# LaunchpadRJ11Baseboard_Mk2.net
KiCad netlist of a schematic drawn in EAGLE
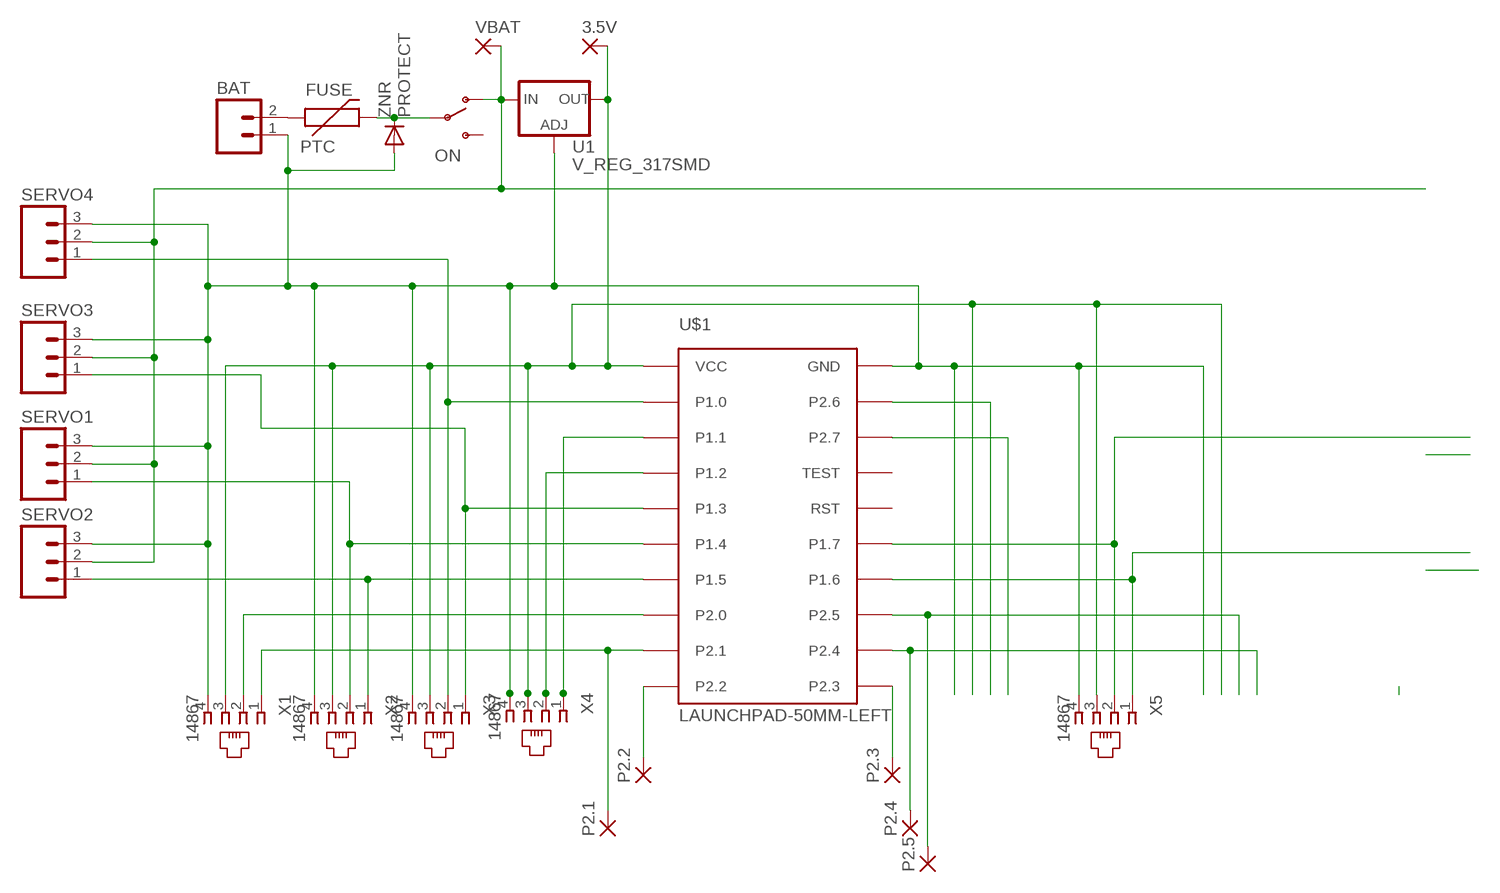
[diagram p0: schematic, sheet 1]

(export (version "E")
  (design (tool "Eeschema 10.0.6"))
  (components
    (comp (ref "3.5V")
      (value "2,15/1,0")
      (footprint "eagle-import:2,15_1,0")
      (libsource (lib "eagle-import") (part "2,15/1,0"))
    )
    (comp (ref "BAT")
      (value "M02PTH")
      (footprint "eagle-import:1X02")
      (libsource (lib "eagle-import") (part "M02PTH"))
    )
    (comp (ref "FUSE")
      (value "PTC")
      (footprint "eagle-import:PTC")
      (libsource (lib "eagle-import") (part "PTCPTH"))
    )
    (comp (ref "ON")
      (value "SWITCH-SPSTPTH")
      (footprint "eagle-import:SWITCH-SPDT")
      (libsource (lib "eagle-import") (part "SWITCH-SPSTPTH"))
    )
    (comp (ref "P2.1")
      (value "2,15/1,0")
      (footprint "eagle-import:2,15_1,0")
      (libsource (lib "eagle-import") (part "2,15/1,0"))
    )
    (comp (ref "P2.2")
      (value "2,15/1,0")
      (footprint "eagle-import:2,15_1,0")
      (libsource (lib "eagle-import") (part "2,15/1,0"))
    )
    (comp (ref "P2.3")
      (value "2,15/1,0")
      (footprint "eagle-import:2,15_1,0")
      (libsource (lib "eagle-import") (part "2,15/1,0"))
    )
    (comp (ref "P2.4")
      (value "2,15/1,0")
      (footprint "eagle-import:2,15_1,0")
      (libsource (lib "eagle-import") (part "2,15/1,0"))
    )
    (comp (ref "P2.5")
      (value "2,15/1,0")
      (footprint "eagle-import:2,15_1,0")
      (libsource (lib "eagle-import") (part "2,15/1,0"))
    )
    (comp (ref "SERVO1")
      (value "M03PTH")
      (footprint "eagle-import:1X03")
      (libsource (lib "eagle-import") (part "M03PTH"))
    )
    (comp (ref "SERVO2")
      (value "M03PTH")
      (footprint "eagle-import:1X03")
      (libsource (lib "eagle-import") (part "M03PTH"))
    )
    (comp (ref "SERVO3")
      (value "M03PTH")
      (footprint "eagle-import:1X03")
      (libsource (lib "eagle-import") (part "M03PTH"))
    )
    (comp (ref "SERVO4")
      (value "M03PTH")
      (footprint "eagle-import:1X03")
      (libsource (lib "eagle-import") (part "M03PTH"))
    )
    (comp (ref "U$1")
      (value "LAUNCHPAD-50MM-LEFT")
      (footprint "eagle-import:LAUNCHPAD-50MM-LEFT")
      (libsource (lib "eagle-import") (part "LAUNCHPAD-50MM-LEFT"))
    )
    (comp (ref "U1")
      (value "V_REG_317SMD")
      (footprint "eagle-import:SOT223")
      (libsource (lib "eagle-import") (part "V_REG_317SMD"))
    )
    (comp (ref "VBAT")
      (value "2,15/1,0")
      (footprint "eagle-import:2,15_1,0")
      (libsource (lib "eagle-import") (part "2,15/1,0"))
    )
    (comp (ref "X1")
      (value "14867")
      (footprint "eagle-import:14867")
      (libsource (lib "eagle-import") (part "14867"))
    )
    (comp (ref "X2")
      (value "14867")
      (footprint "eagle-import:14867")
      (fields (field (name "OC_FARNELL") "unknown") (field (name "OC_NEWARK") "unknown"))
      (libsource (lib "eagle-import") (part "14867"))
    )
    (comp (ref "X3")
      (value "14867")
      (footprint "eagle-import:14867")
      (fields (field (name "OC_FARNELL") "unknown") (field (name "OC_NEWARK") "unknown"))
      (libsource (lib "eagle-import") (part "14867"))
    )
    (comp (ref "X4")
      (value "14867")
      (footprint "eagle-import:14867")
      (fields (field (name "OC_FARNELL") "unknown") (field (name "OC_NEWARK") "unknown"))
      (libsource (lib "eagle-import") (part "14867"))
    )
    (comp (ref "X5")
      (value "14867")
      (footprint "eagle-import:14867")
      (fields (field (name "OC_FARNELL") "unknown") (field (name "OC_NEWARK") "unknown"))
      (libsource (lib "eagle-import") (part "14867"))
    )
    (comp (ref "ZNR")
      (value "PROTECT")
      (footprint "eagle-import:DO41-10")
      (libsource (lib "eagle-import") (part "1N4004"))
    )
  )
  (nets
    (net (code "1") (name "Net-(3.5V-P)") (class "Default")
      (node (ref "3.5V") (pin "1") (pinfunction "P_1") (pintype "passive"))
      (node (ref "U$1") (pin "VCC") (pinfunction "VCC_VCC") (pintype "power_in"))
      (node (ref "U1") (pin "2") (pinfunction "OUT_2") (pintype "output"))
      (node (ref "X1") (pin "3") (pinfunction "3_3") (pintype "passive"))
      (node (ref "X2") (pin "3") (pinfunction "3_3") (pintype "passive"))
      (node (ref "X3") (pin "3") (pinfunction "3_3") (pintype "passive"))
      (node (ref "X4") (pin "3") (pinfunction "3_3") (pintype "passive"))
      (node (ref "X5") (pin "3") (pinfunction "3_3") (pintype "passive"))
    )
    (net (code "2") (name "Net-(FUSE-1)") (class "Default")
      (node (ref "BAT") (pin "2") (pinfunction "2_2") (pintype "passive"))
      (node (ref "FUSE") (pin "P$1") (pinfunction "1_P$1") (pintype "bidirectional"))
    )
    (net (code "3") (name "Net-(FUSE-2)") (class "Default")
      (node (ref "FUSE") (pin "P$2") (pinfunction "2_P$2") (pintype "bidirectional"))
      (node (ref "ON") (pin "2") (pinfunction "P_2") (pintype "passive"))
      (node (ref "ZNR") (pin "C") (pinfunction "C_C") (pintype "passive"))
    )
    (net (code "4") (name "Net-(ON-O)") (class "Default")
      (node (ref "ON") (pin "1") (pinfunction "O_1") (pintype "passive"))
      (node (ref "SERVO1") (pin "2") (pinfunction "2_2") (pintype "passive"))
      (node (ref "SERVO2") (pin "2") (pinfunction "2_2") (pintype "passive"))
      (node (ref "SERVO3") (pin "2") (pinfunction "2_2") (pintype "passive"))
      (node (ref "SERVO4") (pin "2") (pinfunction "2_2") (pintype "passive"))
      (node (ref "U1") (pin "3") (pinfunction "IN_3") (pintype "input"))
      (node (ref "VBAT") (pin "1") (pinfunction "P_1") (pintype "passive"))
    )
    (net (code "5") (name "Net-(P2.1-P)") (class "Default")
      (node (ref "P2.1") (pin "1") (pinfunction "P_1") (pintype "passive"))
      (node (ref "U$1") (pin "P2.1") (pinfunction "P2.1_P2.1") (pintype "bidirectional"))
      (node (ref "X1") (pin "1") (pinfunction "1_1") (pintype "passive"))
    )
    (net (code "6") (name "Net-(P2.2-P)") (class "Default")
      (node (ref "P2.2") (pin "1") (pinfunction "P_1") (pintype "passive"))
      (node (ref "U$1") (pin "P2.2") (pinfunction "P2.2_P2.2") (pintype "bidirectional"))
    )
    (net (code "7") (name "Net-(P2.3-P)") (class "Default")
      (node (ref "P2.3") (pin "1") (pinfunction "P_1") (pintype "passive"))
      (node (ref "U$1") (pin "P2.3") (pinfunction "P2.3_P2.3") (pintype "bidirectional"))
    )
    (net (code "8") (name "Net-(P2.4-P)") (class "Default")
      (node (ref "P2.4") (pin "1") (pinfunction "P_1") (pintype "passive"))
      (node (ref "U$1") (pin "P2.4") (pinfunction "P2.4_P2.4") (pintype "bidirectional"))
    )
    (net (code "9") (name "Net-(P2.5-P)") (class "Default")
      (node (ref "P2.5") (pin "1") (pinfunction "P_1") (pintype "passive"))
      (node (ref "U$1") (pin "P2.5") (pinfunction "P2.5_P2.5") (pintype "bidirectional"))
    )
    (net (code "10") (name "Net-(SERVO1-Pad1)") (class "Default")
      (node (ref "SERVO1") (pin "1") (pinfunction "1_1") (pintype "passive"))
      (node (ref "U$1") (pin "P1.4") (pinfunction "P1.4_P1.4") (pintype "bidirectional"))
      (node (ref "X2") (pin "2") (pinfunction "2_2") (pintype "passive"))
    )
    (net (code "11") (name "Net-(SERVO2-Pad1)") (class "Default")
      (node (ref "SERVO2") (pin "1") (pinfunction "1_1") (pintype "passive"))
      (node (ref "U$1") (pin "P1.5") (pinfunction "P1.5_P1.5") (pintype "bidirectional"))
      (node (ref "X2") (pin "1") (pinfunction "1_1") (pintype "passive"))
    )
    (net (code "12") (name "Net-(SERVO3-Pad1)") (class "Default")
      (node (ref "SERVO3") (pin "1") (pinfunction "1_1") (pintype "passive"))
      (node (ref "U$1") (pin "P1.3") (pinfunction "P1.3_P1.3") (pintype "bidirectional"))
      (node (ref "X3") (pin "1") (pinfunction "1_1") (pintype "passive"))
    )
    (net (code "13") (name "Net-(SERVO4-Pad1)") (class "Default")
      (node (ref "SERVO4") (pin "1") (pinfunction "1_1") (pintype "passive"))
      (node (ref "U$1") (pin "P1.0") (pinfunction "P1.0_P1.0") (pintype "bidirectional"))
      (node (ref "X3") (pin "2") (pinfunction "2_2") (pintype "passive"))
    )
    (net (code "14") (name "Net-(U$1-PadP1.1)") (class "Default")
      (node (ref "U$1") (pin "P1.1") (pinfunction "P1.1_P1.1") (pintype "bidirectional"))
      (node (ref "X4") (pin "1") (pinfunction "1_1") (pintype "passive"))
    )
    (net (code "15") (name "Net-(U$1-PadP1.2)") (class "Default")
      (node (ref "U$1") (pin "P1.2") (pinfunction "P1.2_P1.2") (pintype "bidirectional"))
      (node (ref "X4") (pin "2") (pinfunction "2_2") (pintype "passive"))
    )
    (net (code "16") (name "Net-(U$1-PadP1.6)") (class "Default")
      (node (ref "U$1") (pin "P1.6") (pinfunction "P1.6_P1.6") (pintype "bidirectional"))
      (node (ref "X5") (pin "1") (pinfunction "1_1") (pintype "passive"))
    )
    (net (code "17") (name "Net-(U$1-PadP1.7)") (class "Default")
      (node (ref "U$1") (pin "P1.7") (pinfunction "P1.7_P1.7") (pintype "bidirectional"))
      (node (ref "X5") (pin "2") (pinfunction "2_2") (pintype "passive"))
    )
    (net (code "18") (name "Net-(U$1-PadP2.0)") (class "Default")
      (node (ref "U$1") (pin "P2.0") (pinfunction "P2.0_P2.0") (pintype "bidirectional"))
      (node (ref "X1") (pin "2") (pinfunction "2_2") (pintype "passive"))
    )
    (net (code "19") (name "Net-(U1-ADJ)") (class "Default")
      (node (ref "BAT") (pin "1") (pinfunction "1_1") (pintype "passive"))
      (node (ref "SERVO1") (pin "3") (pinfunction "3_3") (pintype "passive"))
      (node (ref "SERVO2") (pin "3") (pinfunction "3_3") (pintype "passive"))
      (node (ref "SERVO3") (pin "3") (pinfunction "3_3") (pintype "passive"))
      (node (ref "SERVO4") (pin "3") (pinfunction "3_3") (pintype "passive"))
      (node (ref "U$1") (pin "GND") (pinfunction "GND_GND") (pintype "power_in"))
      (node (ref "U1") (pin "1") (pinfunction "ADJ_1") (pintype "input"))
      (node (ref "X1") (pin "4") (pinfunction "4_4") (pintype "passive"))
      (node (ref "X2") (pin "4") (pinfunction "4_4") (pintype "passive"))
      (node (ref "X3") (pin "4") (pinfunction "4_4") (pintype "passive"))
      (node (ref "X4") (pin "4") (pinfunction "4_4") (pintype "passive"))
      (node (ref "X5") (pin "4") (pinfunction "4_4") (pintype "passive"))
      (node (ref "ZNR") (pin "A") (pinfunction "A_A") (pintype "passive"))
    )
    (net (code "20") (name "unconnected-(ON-S-Pad3)") (class "Default")
      (node (ref "ON") (pin "3") (pinfunction "S_3") (pintype "passive"))
    )
    (net (code "21") (name "unconnected-(U$1-PadP2.6)") (class "Default")
      (node (ref "U$1") (pin "P2.6") (pinfunction "P2.6_P2.6") (pintype "bidirectional"))
    )
    (net (code "22") (name "unconnected-(U$1-PadP2.7)") (class "Default")
      (node (ref "U$1") (pin "P2.7") (pinfunction "P2.7_P2.7") (pintype "bidirectional"))
    )
    (net (code "23") (name "unconnected-(U$1-PadRST)") (class "Default")
      (node (ref "U$1") (pin "RST") (pinfunction "RST_RST") (pintype "bidirectional"))
    )
    (net (code "24") (name "unconnected-(U$1-PadTEST)") (class "Default")
      (node (ref "U$1") (pin "TEST") (pinfunction "TEST_TEST") (pintype "bidirectional"))
    )
  )
)
